# main.net
KiCad netlist of a schematic drawn in EAGLE
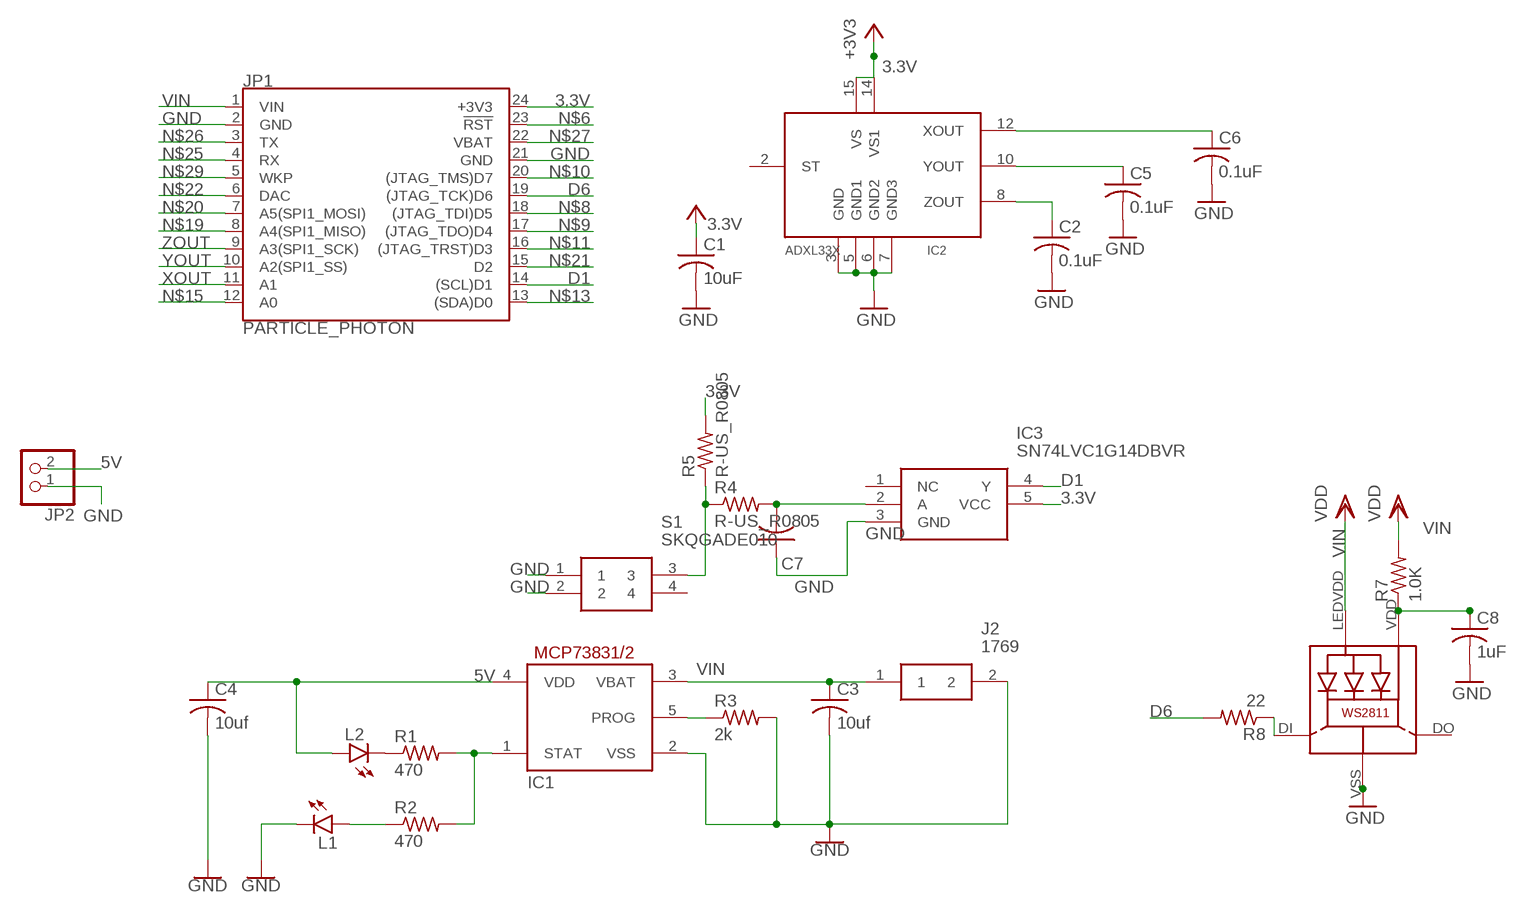
[diagram p0: schematic, sheet 1]

(export (version "E")
  (design (tool "Eeschema 10.0.6"))
  (components
    (comp (ref "C1")
      (value "10uF")
      (footprint "eagle-import:ADAFRUIT_C0805K")
      (libsource (lib "eagle-import") (part "ADAFRUIT_C-USC0805K"))
    )
    (comp (ref "C2")
      (value "0.1uF")
      (footprint "eagle-import:ADAFRUIT_C0805K")
      (libsource (lib "eagle-import") (part "ADAFRUIT_C-USC0805K"))
    )
    (comp (ref "C3")
      (value "10uf")
      (footprint "eagle-import:ADAFRUIT_C0805K")
      (libsource (lib "eagle-import") (part "ADAFRUIT_C-USC0805K"))
    )
    (comp (ref "C4")
      (value "10uf")
      (footprint "eagle-import:ADAFRUIT_C0805K")
      (libsource (lib "eagle-import") (part "ADAFRUIT_C-USC0805K"))
    )
    (comp (ref "C5")
      (value "0.1uF")
      (footprint "eagle-import:ADAFRUIT_C0805K")
      (libsource (lib "eagle-import") (part "ADAFRUIT_C-USC0805K"))
    )
    (comp (ref "C6")
      (value "0.1uF")
      (footprint "eagle-import:ADAFRUIT_C0805K")
      (libsource (lib "eagle-import") (part "ADAFRUIT_C-USC0805K"))
    )
    (comp (ref "C7")
      (value "ADAFRUIT_C-USC0805K")
      (footprint "eagle-import:ADAFRUIT_C0805K")
      (libsource (lib "eagle-import") (part "ADAFRUIT_C-USC0805K"))
    )
    (comp (ref "C8")
      (value "1uF")
      (footprint "eagle-import:ADAFRUIT_C0805K")
      (libsource (lib "eagle-import") (part "ADAFRUIT_C-USC0805K"))
    )
    (comp (ref "IC1")
      (value "MCP73831/OT")
      (footprint "eagle-import:SOT23-5L")
      (libsource (lib "eagle-import") (part "MCP73831/OT"))
    )
    (comp (ref "IC2")
      (value "ADXL33X")
      (footprint "eagle-import:16LCSP")
      (libsource (lib "eagle-import") (part "ADXL33X"))
    )
    (comp (ref "IC3")
      (value "SN74LVC1G14DBVR")
      (footprint "eagle-import:SOT95P280X145-5N")
      (fields (field (name "MOUSER_PART_NUMBER") "595-SN74LVC1G14DBVR"))
      (libsource (lib "eagle-import") (part "SN74LVC1G14DBVR"))
    )
    (comp (ref "J2")
      (value "1769")
      (footprint "eagle-import:1769")
      (fields (field (name "MOUSER_PART_NUMBER") "485-1769"))
      (libsource (lib "eagle-import") (part "1769"))
    )
    (comp (ref "JP1")
      (value "PARTICLE_PHOTON")
      (footprint "eagle-import:PARTICLE_PHOTON")
      (libsource (lib "eagle-import") (part "PARTICLE_PHOTON"))
    )
    (comp (ref "JP2")
      (value "PINHD-1X2")
      (footprint "eagle-import:1X02")
      (libsource (lib "eagle-import") (part "PINHD-1X2"))
    )
    (comp (ref "L1")
      (value "green")
      (footprint "eagle-import:FKIT-LED-1206")
      (libsource (lib "eagle-import") (part "LED-FKIT-1206"))
    )
    (comp (ref "L2")
      (value "blue")
      (footprint "eagle-import:FKIT-LED-1206")
      (libsource (lib "eagle-import") (part "LED-FKIT-1206"))
    )
    (comp (ref "LED1")
      (value "WS28115050")
      (footprint "eagle-import:WS28115050")
      (libsource (lib "eagle-import") (part "WS28115050"))
    )
    (comp (ref "R1")
      (value "470")
      (footprint "eagle-import:R0805")
      (libsource (lib "eagle-import") (part "R-US_R0805"))
    )
    (comp (ref "R2")
      (value "470")
      (footprint "eagle-import:R0805")
      (libsource (lib "eagle-import") (part "R-US_R0805"))
    )
    (comp (ref "R3")
      (value "2k")
      (footprint "eagle-import:R0805")
      (libsource (lib "eagle-import") (part "R-US_R0805"))
    )
    (comp (ref "R4")
      (value "R-US_R0805")
      (footprint "eagle-import:R0805")
      (libsource (lib "eagle-import") (part "R-US_R0805"))
    )
    (comp (ref "R5")
      (value "R-US_R0805")
      (footprint "eagle-import:R0805")
      (libsource (lib "eagle-import") (part "R-US_R0805"))
    )
    (comp (ref "R7")
      (value "1.0K")
      (footprint "eagle-import:R0805")
      (libsource (lib "eagle-import") (part "R-US_R0805"))
    )
    (comp (ref "R8")
      (value "22")
      (footprint "eagle-import:R0805")
      (libsource (lib "eagle-import") (part "R-US_R0805"))
    )
    (comp (ref "S1")
      (value "SKQGADE010")
      (footprint "eagle-import:SKQGAKE010")
      (fields (field (name "MOUSER_PART_NUMBER") "688-SKQGAD") (field (name "RS_PART_NUMBER") "7582067"))
      (libsource (lib "eagle-import") (part "SKQGADE010"))
    )
  )
  (nets
    (net (code "1") (name "+3V3") (class "Default")
      (node (ref "C1") (pin "1") (pinfunction "1_1") (pintype "passive"))
      (node (ref "IC2") (pin "14") (pinfunction "VS1_14") (pintype "power_in"))
      (node (ref "IC2") (pin "15") (pinfunction "VS_15") (pintype "power_in"))
      (node (ref "IC3") (pin "5") (pinfunction "VCC_5") (pintype "bidirectional"))
      (node (ref "JP1") (pin "24") (pinfunction "+3V3_24") (pintype "power_in"))
      (node (ref "R5") (pin "2") (pinfunction "2_2") (pintype "passive"))
    )
    (net (code "2") (name "/5V") (class "Default")
      (node (ref "C4") (pin "1") (pinfunction "1_1") (pintype "passive"))
      (node (ref "IC1") (pin "4") (pinfunction "VDD_4") (pintype "power_in"))
      (node (ref "JP2") (pin "2") (pinfunction "2_2") (pintype "passive"))
      (node (ref "L2") (pin "A") (pinfunction "A_A") (pintype "passive"))
    )
    (net (code "3") (name "/D1") (class "Default")
      (node (ref "IC3") (pin "4") (pinfunction "Y_4") (pintype "bidirectional"))
      (node (ref "JP1") (pin "14") (pinfunction "(SCL)D1_14") (pintype "bidirectional"))
    )
    (net (code "4") (name "/D6") (class "Default")
      (node (ref "JP1") (pin "19") (pinfunction "(JTAG_TCK)D6_19") (pintype "bidirectional"))
      (node (ref "R8") (pin "2") (pinfunction "2_2") (pintype "passive"))
    )
    (net (code "5") (name "/N$6") (class "Default")
      (node (ref "JP1") (pin "23") (pinfunction "~{RST}_23") (pintype "bidirectional"))
    )
    (net (code "6") (name "/N$8") (class "Default")
      (node (ref "JP1") (pin "18") (pinfunction "(JTAG_TDI)D5_18") (pintype "bidirectional"))
    )
    (net (code "7") (name "/N$9") (class "Default")
      (node (ref "JP1") (pin "17") (pinfunction "(JTAG_TDO)D4_17") (pintype "bidirectional"))
    )
    (net (code "8") (name "/N$10") (class "Default")
      (node (ref "JP1") (pin "20") (pinfunction "(JTAG_TMS)D7_20") (pintype "bidirectional"))
    )
    (net (code "9") (name "/N$11") (class "Default")
      (node (ref "JP1") (pin "16") (pinfunction "(JTAG_TRST)D3_16") (pintype "bidirectional"))
    )
    (net (code "10") (name "/N$13") (class "Default")
      (node (ref "JP1") (pin "13") (pinfunction "(SDA)D0_13") (pintype "bidirectional"))
    )
    (net (code "11") (name "/N$15") (class "Default")
      (node (ref "JP1") (pin "12") (pinfunction "A0_12") (pintype "bidirectional"))
    )
    (net (code "12") (name "/N$19") (class "Default")
      (node (ref "JP1") (pin "8") (pinfunction "A4(SPI1_MISO)_8") (pintype "bidirectional"))
    )
    (net (code "13") (name "/N$20") (class "Default")
      (node (ref "JP1") (pin "7") (pinfunction "A5(SPI1_MOSI)_7") (pintype "bidirectional"))
    )
    (net (code "14") (name "/N$21") (class "Default")
      (node (ref "JP1") (pin "15") (pinfunction "D2_15") (pintype "bidirectional"))
    )
    (net (code "15") (name "/N$22") (class "Default")
      (node (ref "JP1") (pin "6") (pinfunction "DAC_6") (pintype "bidirectional"))
    )
    (net (code "16") (name "/N$25") (class "Default")
      (node (ref "JP1") (pin "4") (pinfunction "RX_4") (pintype "bidirectional"))
    )
    (net (code "17") (name "/N$26") (class "Default")
      (node (ref "JP1") (pin "3") (pinfunction "TX_3") (pintype "bidirectional"))
    )
    (net (code "18") (name "/N$27") (class "Default")
      (node (ref "JP1") (pin "22") (pinfunction "VBAT_22") (pintype "power_in"))
    )
    (net (code "19") (name "/N$29") (class "Default")
      (node (ref "JP1") (pin "5") (pinfunction "WKP_5") (pintype "bidirectional"))
    )
    (net (code "20") (name "/XOUT") (class "Default")
      (node (ref "C6") (pin "1") (pinfunction "1_1") (pintype "passive"))
      (node (ref "IC2") (pin "12") (pinfunction "XOUT_12") (pintype "output"))
      (node (ref "JP1") (pin "11") (pinfunction "A1_11") (pintype "bidirectional"))
    )
    (net (code "21") (name "/YOUT") (class "Default")
      (node (ref "C5") (pin "1") (pinfunction "1_1") (pintype "passive"))
      (node (ref "IC2") (pin "10") (pinfunction "YOUT_10") (pintype "output"))
      (node (ref "JP1") (pin "10") (pinfunction "A2(SPI1_SS)_10") (pintype "bidirectional"))
    )
    (net (code "22") (name "/ZOUT") (class "Default")
      (node (ref "C2") (pin "1") (pinfunction "1_1") (pintype "passive"))
      (node (ref "IC2") (pin "8") (pinfunction "ZOUT_8") (pintype "output"))
      (node (ref "JP1") (pin "9") (pinfunction "A3(SPI1_SCK)_9") (pintype "bidirectional"))
    )
    (net (code "23") (name "GND") (class "Default")
      (node (ref "C1") (pin "2") (pinfunction "2_2") (pintype "passive"))
      (node (ref "C2") (pin "2") (pinfunction "2_2") (pintype "passive"))
      (node (ref "C3") (pin "2") (pinfunction "2_2") (pintype "passive"))
      (node (ref "C4") (pin "2") (pinfunction "2_2") (pintype "passive"))
      (node (ref "C5") (pin "2") (pinfunction "2_2") (pintype "passive"))
      (node (ref "C6") (pin "2") (pinfunction "2_2") (pintype "passive"))
      (node (ref "C7") (pin "1") (pinfunction "1_1") (pintype "passive"))
      (node (ref "C8") (pin "2") (pinfunction "2_2") (pintype "passive"))
      (node (ref "IC1") (pin "2") (pinfunction "VSS_2") (pintype "power_in"))
      (node (ref "IC2") (pin "3") (pinfunction "GND_3") (pintype "power_in"))
      (node (ref "IC2") (pin "5") (pinfunction "GND1_5") (pintype "power_in"))
      (node (ref "IC2") (pin "6") (pinfunction "GND2_6") (pintype "power_in"))
      (node (ref "IC2") (pin "7") (pinfunction "GND3_7") (pintype "power_in"))
      (node (ref "IC3") (pin "3") (pinfunction "GND_3") (pintype "bidirectional"))
      (node (ref "J2") (pin "2") (pinfunction "2_2") (pintype "bidirectional"))
      (node (ref "JP1") (pin "2") (pinfunction "GND_2") (pintype "power_in"))
      (node (ref "JP1") (pin "21") (pinfunction "GND_21") (pintype "power_in"))
      (node (ref "JP2") (pin "1") (pinfunction "1_1") (pintype "passive"))
      (node (ref "L1") (pin "C") (pinfunction "C_C") (pintype "passive"))
      (node (ref "LED1") (pin "VSS") (pinfunction "GND_VSS") (pintype "power_in"))
      (node (ref "R3") (pin "2") (pinfunction "2_2") (pintype "passive"))
      (node (ref "S1") (pin "1") (pinfunction "1_1") (pintype "bidirectional"))
      (node (ref "S1") (pin "2") (pinfunction "2_2") (pintype "bidirectional"))
    )
    (net (code "24") (name "Net-(C8-Pad1)") (class "Default")
      (node (ref "C8") (pin "1") (pinfunction "1_1") (pintype "passive"))
      (node (ref "LED1") (pin "VDD") (pinfunction "VDD_VDD") (pintype "power_in"))
      (node (ref "R7") (pin "1") (pinfunction "1_1") (pintype "passive"))
    )
    (net (code "25") (name "Net-(IC1-PROG)") (class "Default")
      (node (ref "IC1") (pin "5") (pinfunction "PROG_5") (pintype "input"))
      (node (ref "R3") (pin "1") (pinfunction "1_1") (pintype "passive"))
    )
    (net (code "26") (name "Net-(IC1-STAT)") (class "Default")
      (node (ref "IC1") (pin "1") (pinfunction "STAT_1") (pintype "output"))
      (node (ref "R1") (pin "2") (pinfunction "2_2") (pintype "passive"))
      (node (ref "R2") (pin "2") (pinfunction "2_2") (pintype "passive"))
    )
    (net (code "27") (name "Net-(IC3-A)") (class "Default")
      (node (ref "C7") (pin "2") (pinfunction "2_2") (pintype "passive"))
      (node (ref "IC3") (pin "2") (pinfunction "A_2") (pintype "bidirectional"))
      (node (ref "R4") (pin "2") (pinfunction "2_2") (pintype "passive"))
    )
    (net (code "28") (name "Net-(L1-PadA)") (class "Default")
      (node (ref "L1") (pin "A") (pinfunction "A_A") (pintype "passive"))
      (node (ref "R2") (pin "1") (pinfunction "1_1") (pintype "passive"))
    )
    (net (code "29") (name "Net-(L2-PadC)") (class "Default")
      (node (ref "L2") (pin "C") (pinfunction "C_C") (pintype "passive"))
      (node (ref "R1") (pin "1") (pinfunction "1_1") (pintype "passive"))
    )
    (net (code "30") (name "Net-(LED1-PadDI)") (class "Default")
      (node (ref "LED1") (pin "DI") (pinfunction "DI_DI") (pintype "input"))
      (node (ref "R8") (pin "1") (pinfunction "1_1") (pintype "passive"))
    )
    (net (code "31") (name "Net-(R4-Pad1)") (class "Default")
      (node (ref "R4") (pin "1") (pinfunction "1_1") (pintype "passive"))
      (node (ref "R5") (pin "1") (pinfunction "1_1") (pintype "passive"))
      (node (ref "S1") (pin "3") (pinfunction "3_3") (pintype "bidirectional"))
    )
    (net (code "32") (name "VDD") (class "Default")
      (node (ref "C3") (pin "1") (pinfunction "1_1") (pintype "passive"))
      (node (ref "IC1") (pin "3") (pinfunction "VBAT_3") (pintype "bidirectional"))
      (node (ref "J2") (pin "1") (pinfunction "1_1") (pintype "bidirectional"))
      (node (ref "JP1") (pin "1") (pinfunction "VIN_1") (pintype "power_in"))
      (node (ref "LED1") (pin "LEDVDD") (pinfunction "LEDVDD_LEDVDD") (pintype "power_in"))
      (node (ref "R7") (pin "2") (pinfunction "2_2") (pintype "passive"))
    )
    (net (code "33") (name "unconnected-(IC2-ST-Pad2)") (class "Default")
      (node (ref "IC2") (pin "2") (pinfunction "ST_2") (pintype "input"))
    )
    (net (code "34") (name "unconnected-(IC3-NC-Pad1)") (class "Default")
      (node (ref "IC3") (pin "1") (pinfunction "NC_1") (pintype "no_connect"))
    )
    (net (code "35") (name "unconnected-(LED1-PadDO)") (class "Default")
      (node (ref "LED1") (pin "DO") (pinfunction "DO_DO") (pintype "output"))
    )
    (net (code "36") (name "unconnected-(S1-Pad4)") (class "Default")
      (node (ref "S1") (pin "4") (pinfunction "4_4") (pintype "bidirectional"))
    )
  )
)
